# control_board_v006_Rev5.net
KiCad netlist of a schematic drawn in EAGLE
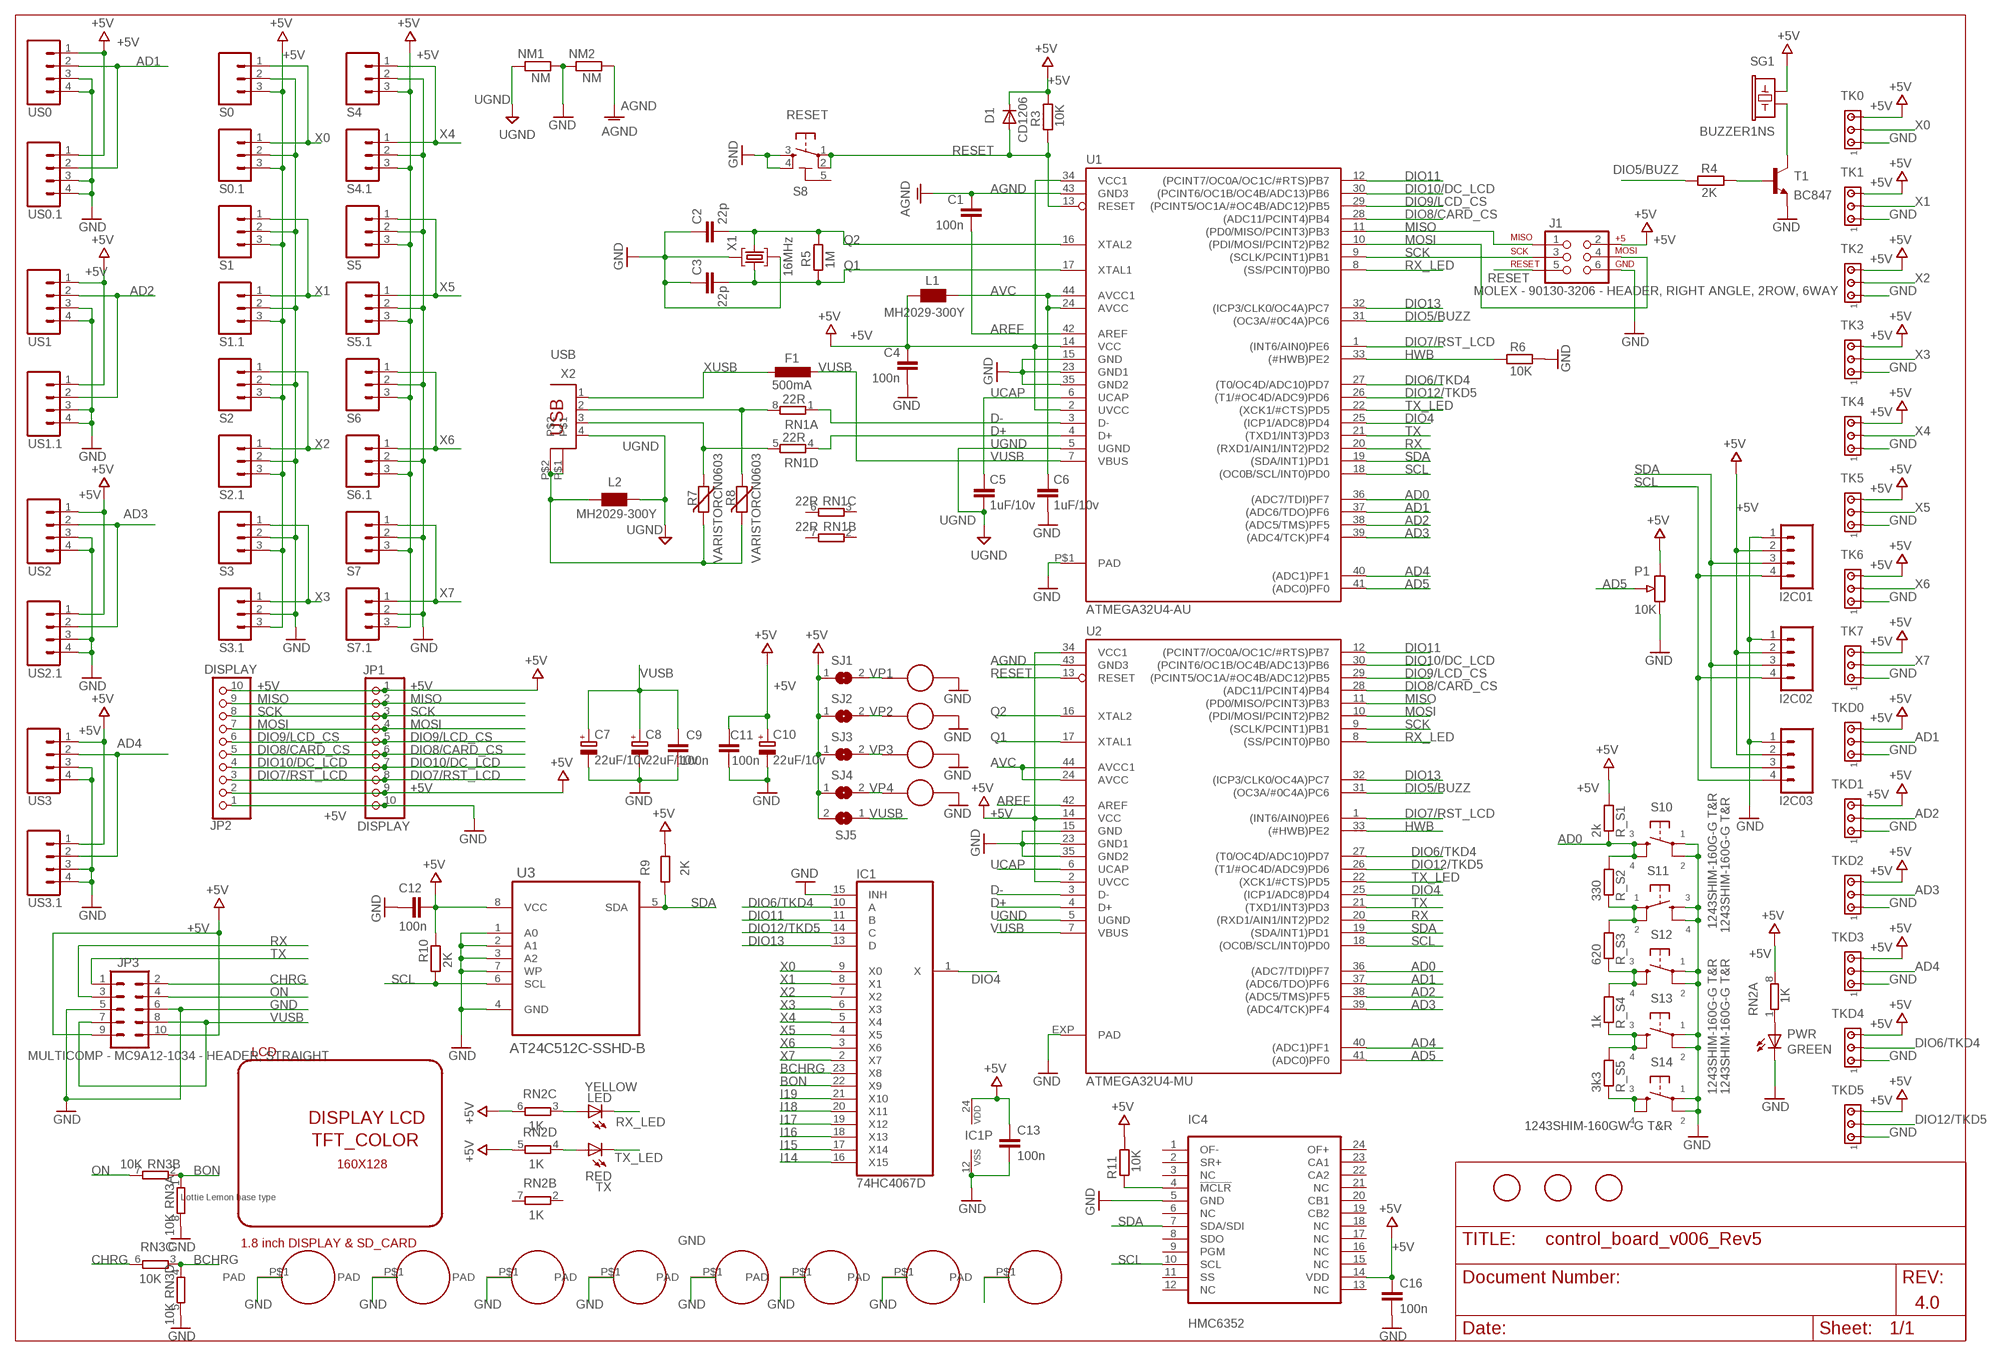
[diagram p0: schematic, sheet 1]

(export (version "E")
  (design (tool "Eeschema 10.0.6"))
  (components
    (comp (ref "1")
      (value "FIDUCIALMOUNT")
      (footprint "eagle-import:FIDUCIA-MOUNT")
      (libsource (lib "eagle-import") (part "FIDUCIALMOUNT"))
    )
    (comp (ref "2")
      (value "FIDUCIALMOUNT")
      (footprint "eagle-import:FIDUCIA-MOUNT")
      (libsource (lib "eagle-import") (part "FIDUCIALMOUNT"))
    )
    (comp (ref "3")
      (value "FIDUCIALMOUNT")
      (footprint "eagle-import:FIDUCIA-MOUNT")
      (libsource (lib "eagle-import") (part "FIDUCIALMOUNT"))
    )
    (comp (ref "C1")
      (value "100n")
      (footprint "eagle-import:C0603-ROUND")
      (libsource (lib "eagle-import") (part "C-EUC0603"))
    )
    (comp (ref "C2")
      (value "22p")
      (footprint "eagle-import:C0603-ROUND")
      (libsource (lib "eagle-import") (part "C-EUC0603"))
    )
    (comp (ref "C3")
      (value "22p")
      (footprint "eagle-import:C0603-ROUND")
      (libsource (lib "eagle-import") (part "C-EUC0603"))
    )
    (comp (ref "C4")
      (value "100n")
      (footprint "eagle-import:C0603-ROUND")
      (libsource (lib "eagle-import") (part "C-EUC0603"))
    )
    (comp (ref "C5")
      (value "1uF/10v")
      (footprint "eagle-import:C0603-ROUND")
      (libsource (lib "eagle-import") (part "C-EUC0603"))
    )
    (comp (ref "C6")
      (value "1uF/10v")
      (footprint "eagle-import:C0603-ROUND")
      (libsource (lib "eagle-import") (part "C-EUC0603"))
    )
    (comp (ref "C7")
      (value "22uF/10v")
      (footprint "eagle-import:SMC_B")
      (libsource (lib "eagle-import") (part "CPOL-EUSMCB"))
    )
    (comp (ref "C8")
      (value "22uF/10v")
      (footprint "eagle-import:SMC_B")
      (libsource (lib "eagle-import") (part "CPOL-EUSMCB"))
    )
    (comp (ref "C9")
      (value "100n")
      (footprint "eagle-import:C0603-ROUND")
      (libsource (lib "eagle-import") (part "C-EUC0603"))
    )
    (comp (ref "C10")
      (value "22uF/10v")
      (footprint "eagle-import:SMC_B")
      (libsource (lib "eagle-import") (part "CPOL-EUSMCB"))
    )
    (comp (ref "C11")
      (value "100n")
      (footprint "eagle-import:C0603-ROUND")
      (libsource (lib "eagle-import") (part "C-EUC0603"))
    )
    (comp (ref "C12")
      (value "100n")
      (footprint "eagle-import:C0603-ROUND")
      (libsource (lib "eagle-import") (part "C-EUC0603"))
    )
    (comp (ref "C13")
      (value "100n")
      (footprint "eagle-import:C0603-ROUND")
      (libsource (lib "eagle-import") (part "C-EUC0603"))
    )
    (comp (ref "C16")
      (value "100n")
      (footprint "eagle-import:C0603-ROUND")
      (libsource (lib "eagle-import") (part "C-EUC0603"))
    )
    (comp (ref "D1")
      (value "CD1206")
      (footprint "eagle-import:MINIMELF")
      (libsource (lib "eagle-import") (part "DIODE-MINIMELF"))
    )
    (comp (ref "F1")
      (value "500mA")
      (footprint "eagle-import:L1812")
      (libsource (lib "eagle-import") (part "L-EUL1812"))
    )
    (comp (ref "G1")
      (value "LOTTIE_LEMON_BASE_TYPE")
      (footprint "eagle-import:BASE_ROBOT_001")
      (libsource (lib "eagle-import") (part "LOTTIE_LEMON_BASE_TYPE"))
    )
    (comp (ref "H1")
      (value "2.5-MOUNTING-HOLE")
      (footprint "eagle-import:2.5PAD")
      (libsource (lib "eagle-import") (part "2.5-MOUNTING-HOLE"))
    )
    (comp (ref "H2")
      (value "2.5-MOUNTING-HOLE")
      (footprint "eagle-import:2.5PAD")
      (libsource (lib "eagle-import") (part "2.5-MOUNTING-HOLE"))
    )
    (comp (ref "H3")
      (value "2.5-MOUNTING-HOLE")
      (footprint "eagle-import:2.5PAD")
      (libsource (lib "eagle-import") (part "2.5-MOUNTING-HOLE"))
    )
    (comp (ref "H4")
      (value "2.5-MOUNTING-HOLE")
      (footprint "eagle-import:2.5PAD")
      (libsource (lib "eagle-import") (part "2.5-MOUNTING-HOLE"))
    )
    (comp (ref "H5")
      (value "2.5-MOUNTING-HOLE")
      (footprint "eagle-import:2.5PAD")
      (libsource (lib "eagle-import") (part "2.5-MOUNTING-HOLE"))
    )
    (comp (ref "H6")
      (value "2.5-MOUNTING-HOLE")
      (footprint "eagle-import:2.5PAD")
      (libsource (lib "eagle-import") (part "2.5-MOUNTING-HOLE"))
    )
    (comp (ref "H7")
      (value "2.5-MOUNTING-HOLE")
      (footprint "eagle-import:2.5PAD")
      (libsource (lib "eagle-import") (part "2.5-MOUNTING-HOLE"))
    )
    (comp (ref "H8")
      (value "2.5-MOUNTING-HOLE")
      (footprint "eagle-import:2.5PAD")
      (libsource (lib "eagle-import") (part "2.5-MOUNTING-HOLE"))
    )
    (comp (ref "I2C01")
      (value "M04PTH")
      (footprint "eagle-import:1X04")
      (libsource (lib "eagle-import") (part "M04PTH"))
    )
    (comp (ref "I2C02")
      (value "M04PTH")
      (footprint "eagle-import:1X04")
      (libsource (lib "eagle-import") (part "M04PTH"))
    )
    (comp (ref "I2C03")
      (value "M04PTH")
      (footprint "eagle-import:1X04")
      (libsource (lib "eagle-import") (part "M04PTH"))
    )
    (comp (ref "IC1")
      (value "74HC4067D")
      (footprint "eagle-import:SO24W")
      (libsource (lib "eagle-import") (part "4067D"))
    )
    (comp (ref "IC4")
      (value "HMC6352")
      (footprint "eagle-import:HMC6352")
      (libsource (lib "eagle-import") (part "HMC6352"))
    )
    (comp (ref "J1")
      (value "MOLEX - 90130-3206 - HEADER, RIGHT ANGLE, 2ROW, 6WAY")
      (footprint "eagle-import:2X3")
      (libsource (lib "eagle-import") (part "AVR_SPI_PRG_6PTH"))
    )
    (comp (ref "JP1")
      (value "DISPLAY")
      (footprint "eagle-import:1X10-TH")
      (libsource (lib "eagle-import") (part "PINHD-1X10TH"))
    )
    (comp (ref "JP2")
      (value "DISPLAY")
      (footprint "eagle-import:1X10-TH")
      (libsource (lib "eagle-import") (part "PINHD-1X10TH"))
    )
    (comp (ref "JP3")
      (value "MULTICOMP - MC9A12-1034 - HEADER, STRAIGHT")
      (footprint "eagle-import:2X5-SHROUDED_LOCK")
      (libsource (lib "eagle-import") (part "M05X2SHD_LOCK"))
    )
    (comp (ref "L1")
      (value "MH2029-300Y")
      (footprint "eagle-import:0805")
      (libsource (lib "eagle-import") (part "WE-CBF_0805"))
    )
    (comp (ref "L2")
      (value "MH2029-300Y")
      (footprint "eagle-import:0805")
      (libsource (lib "eagle-import") (part "WE-CBF_0805"))
    )
    (comp (ref "LCD")
      (value "1.8 inch DISPLAY & SD_CARD")
      (footprint "eagle-import:1.8-LCD")
      (libsource (lib "eagle-import") (part "1.8-COLOR_TFT-LCD_DISPLAY_&_MICRO-SD"))
    )
    (comp (ref "LED")
      (value "YELLOW")
      (footprint "eagle-import:CHIP-LED0805")
      (libsource (lib "eagle-import") (part "LEDCHIP-LED0805"))
    )
    (comp (ref "NM1")
      (value "NM")
      (footprint "eagle-import:R0805")
      (libsource (lib "eagle-import") (part "resistor_R-EU_R0805"))
    )
    (comp (ref "NM2")
      (value "NM")
      (footprint "eagle-import:R0805")
      (libsource (lib "eagle-import") (part "resistor_R-EU_R0805"))
    )
    (comp (ref "P1")
      (value "10K")
      (footprint "eagle-import:POT-V")
      (libsource (lib "eagle-import") (part "POT-VERTICAL"))
    )
    (comp (ref "PTZ1")
      (value "LOTTIE_LEMON_PADS_SUP")
      (footprint "eagle-import:PADS_LOTTIE_LEMON_SUP")
      (libsource (lib "eagle-import") (part "LOTTIE_LEMON_PADS_SUP"))
    )
    (comp (ref "PTZ2")
      (value "LOTTIE_LEMON_PADS_SUP")
      (footprint "eagle-import:PADS_LOTTIE_LEMON_SUP")
      (libsource (lib "eagle-import") (part "LOTTIE_LEMON_PADS_SUP"))
    )
    (comp (ref "PTZ3")
      (value "LOTTIE_LEMON_PADS_SUP1")
      (footprint "eagle-import:PADS_LOTTIE_LEMON_SUP")
      (libsource (lib "eagle-import") (part "LOTTIE_LEMON_PADS_SUP1"))
    )
    (comp (ref "PTZ4")
      (value "LOTTIE_LEMON_PADS_SUP1")
      (footprint "eagle-import:PADS_LOTTIE_LEMON_SUP")
      (libsource (lib "eagle-import") (part "LOTTIE_LEMON_PADS_SUP1"))
    )
    (comp (ref "PWR")
      (value "LEDCHIP-LED0805")
      (footprint "eagle-import:CHIP-LED0805")
      (libsource (lib "eagle-import") (part "LEDCHIP-LED0805"))
    )
    (comp (ref "R3")
      (value "10K")
      (footprint "eagle-import:R0603-ROUND")
      (libsource (lib "eagle-import") (part "R-EU_R0603"))
    )
    (comp (ref "R4")
      (value "2K")
      (footprint "eagle-import:R0603-ROUND")
      (libsource (lib "eagle-import") (part "R-EU_R0603"))
    )
    (comp (ref "R5")
      (value "1M")
      (footprint "eagle-import:R0603-ROUND")
      (libsource (lib "eagle-import") (part "R-EU_R0603"))
    )
    (comp (ref "R6")
      (value "10K")
      (footprint "eagle-import:R0603-ROUND")
      (libsource (lib "eagle-import") (part "R-EU_R0603"))
    )
    (comp (ref "R7")
      (value "VARISTORCN0603")
      (footprint "eagle-import:CT_CN0603")
      (libsource (lib "eagle-import") (part "VARISTORCN0603"))
    )
    (comp (ref "R8")
      (value "VARISTORCN0603")
      (footprint "eagle-import:CT_CN0603")
      (libsource (lib "eagle-import") (part "VARISTORCN0603"))
    )
    (comp (ref "R9")
      (value "2K")
      (footprint "eagle-import:R0603-ROUND")
      (libsource (lib "eagle-import") (part "R-EU_R0603"))
    )
    (comp (ref "R10")
      (value "2K")
      (footprint "eagle-import:R0603-ROUND")
      (libsource (lib "eagle-import") (part "R-EU_R0603"))
    )
    (comp (ref "R11")
      (value "10K")
      (footprint "eagle-import:R0603-ROUND")
      (libsource (lib "eagle-import") (part "R-EU_R0603"))
    )
    (comp (ref "RN1")
      (value "22R")
      (footprint "eagle-import:CAY16")
      (fields (field (name "OC_FARNELL") "unknown") (field (name "OC_NEWARK") "unknown"))
      (libsource (lib "eagle-import") (part "4R-NCAY16"))
    )
    (comp (ref "RN2")
      (value "1K")
      (footprint "eagle-import:CAY16")
      (libsource (lib "eagle-import") (part "4R-NCAY16"))
    )
    (comp (ref "RN3")
      (value "10K")
      (footprint "eagle-import:CAY16")
      (fields (field (name "OC_FARNELL") "unknown") (field (name "OC_NEWARK") "unknown"))
      (libsource (lib "eagle-import") (part "4R-NCAY16"))
    )
    (comp (ref "R_S1")
      (value "2k")
      (footprint "eagle-import:R0603-ROUND")
      (libsource (lib "eagle-import") (part "R-EU_R0603"))
    )
    (comp (ref "R_S2")
      (value "330")
      (footprint "eagle-import:R0603-ROUND")
      (libsource (lib "eagle-import") (part "R-EU_R0603"))
    )
    (comp (ref "R_S3")
      (value "620")
      (footprint "eagle-import:R0603-ROUND")
      (libsource (lib "eagle-import") (part "R-EU_R0603"))
    )
    (comp (ref "R_S4")
      (value "1k")
      (footprint "eagle-import:R0603-ROUND")
      (libsource (lib "eagle-import") (part "R-EU_R0603"))
    )
    (comp (ref "R_S5")
      (value "3k3")
      (footprint "eagle-import:R0603-ROUND")
      (libsource (lib "eagle-import") (part "R-EU_R0603"))
    )
    (comp (ref "S0")
      (value "M03PTH")
      (footprint "eagle-import:1X03")
      (libsource (lib "eagle-import") (part "M03PTH"))
    )
    (comp (ref "S0.1")
      (value "M03PTH")
      (footprint "eagle-import:1X03")
      (libsource (lib "eagle-import") (part "M03PTH"))
    )
    (comp (ref "S1")
      (value "M03PTH")
      (footprint "eagle-import:1X03")
      (libsource (lib "eagle-import") (part "M03PTH"))
    )
    (comp (ref "S1.1")
      (value "M03PTH")
      (footprint "eagle-import:1X03")
      (libsource (lib "eagle-import") (part "M03PTH"))
    )
    (comp (ref "S2")
      (value "M03PTH")
      (footprint "eagle-import:1X03")
      (libsource (lib "eagle-import") (part "M03PTH"))
    )
    (comp (ref "S2.1")
      (value "M03PTH")
      (footprint "eagle-import:1X03")
      (libsource (lib "eagle-import") (part "M03PTH"))
    )
    (comp (ref "S3")
      (value "M03PTH")
      (footprint "eagle-import:1X03")
      (libsource (lib "eagle-import") (part "M03PTH"))
    )
    (comp (ref "S3.1")
      (value "M03PTH")
      (footprint "eagle-import:1X03")
      (libsource (lib "eagle-import") (part "M03PTH"))
    )
    (comp (ref "S4")
      (value "M03PTH")
      (footprint "eagle-import:1X03")
      (libsource (lib "eagle-import") (part "M03PTH"))
    )
    (comp (ref "S4.1")
      (value "M03PTH")
      (footprint "eagle-import:1X03")
      (libsource (lib "eagle-import") (part "M03PTH"))
    )
    (comp (ref "S5")
      (value "M03PTH")
      (footprint "eagle-import:1X03")
      (libsource (lib "eagle-import") (part "M03PTH"))
    )
    (comp (ref "S5.1")
      (value "M03PTH")
      (footprint "eagle-import:1X03")
      (libsource (lib "eagle-import") (part "M03PTH"))
    )
    (comp (ref "S6")
      (value "M03PTH")
      (footprint "eagle-import:1X03")
      (libsource (lib "eagle-import") (part "M03PTH"))
    )
    (comp (ref "S6.1")
      (value "M03PTH")
      (footprint "eagle-import:1X03")
      (libsource (lib "eagle-import") (part "M03PTH"))
    )
    (comp (ref "S7")
      (value "M03PTH")
      (footprint "eagle-import:1X03")
      (libsource (lib "eagle-import") (part "M03PTH"))
    )
    (comp (ref "S7.1")
      (value "M03PTH")
      (footprint "eagle-import:1X03")
      (libsource (lib "eagle-import") (part "M03PTH"))
    )
    (comp (ref "S8")
      (value "RESET")
      (footprint "eagle-import:TS42")
      (libsource (lib "eagle-import") (part "TS42"))
    )
    (comp (ref "S10")
      (value "1243SHIM-160G-G T&R")
      (footprint "eagle-import:TACTILE-SMD-12MM")
      (libsource (lib "eagle-import") (part "TACTILE_SWITCHTACTILE_SWITCH_SMD-12MM"))
    )
    (comp (ref "S11")
      (value "1243SHIM-160G-G T&R")
      (footprint "eagle-import:TACTILE-SMD-12MM")
      (libsource (lib "eagle-import") (part "TACTILE_SWITCHTACTILE_SWITCH_SMD-12MM"))
    )
    (comp (ref "S12")
      (value "1243SHIM-160G-G T&R")
      (footprint "eagle-import:TACTILE-SMD-12MM")
      (libsource (lib "eagle-import") (part "TACTILE_SWITCHTACTILE_SWITCH_SMD-12MM"))
    )
    (comp (ref "S13")
      (value "1243SHIM-160G-G T&R")
      (footprint "eagle-import:TACTILE-SMD-12MM")
      (libsource (lib "eagle-import") (part "TACTILE_SWITCHTACTILE_SWITCH_SMD-12MM"))
    )
    (comp (ref "S14")
      (value "1243SHIM-160GW-G T&R")
      (footprint "eagle-import:TACTILE-SMD-12MM")
      (libsource (lib "eagle-import") (part "TACTILE_SWITCHTACTILE_SWITCH_SMD-12MM"))
    )
    (comp (ref "SG1")
      (value "BUZZER1NS")
      (footprint "eagle-import:BUZZER-12MM-NS")
      (libsource (lib "eagle-import") (part "BUZZER1NS"))
    )
    (comp (ref "SJ1") (value "SJ") (footprint "eagle-import:SJ") (libsource (lib "eagle-import") (part "SJ")))
    (comp (ref "SJ2") (value "SJ") (footprint "eagle-import:SJ") (libsource (lib "eagle-import") (part "SJ")))
    (comp (ref "SJ3") (value "SJ") (footprint "eagle-import:SJ") (libsource (lib "eagle-import") (part "SJ")))
    (comp (ref "SJ4") (value "SJ") (footprint "eagle-import:SJ") (libsource (lib "eagle-import") (part "SJ")))
    (comp (ref "SJ5")
      (value "SJL")
      (footprint "eagle-import:SJL")
      (libsource (lib "eagle-import") (part "SJL"))
    )
    (comp (ref "T1")
      (value "BC847")
      (footprint "eagle-import:SOT23")
      (libsource (lib "eagle-import") (part "BC847"))
    )
    (comp (ref "TK0")
      (value "MTA03-100")
      (footprint "eagle-import:10X03MTA")
      (libsource (lib "eagle-import") (part "MTA03-100"))
    )
    (comp (ref "TK1")
      (value "MTA03-100")
      (footprint "eagle-import:10X03MTA")
      (libsource (lib "eagle-import") (part "MTA03-100"))
    )
    (comp (ref "TK2")
      (value "MTA03-100")
      (footprint "eagle-import:10X03MTA")
      (libsource (lib "eagle-import") (part "MTA03-100"))
    )
    (comp (ref "TK3")
      (value "MTA03-100")
      (footprint "eagle-import:10X03MTA")
      (libsource (lib "eagle-import") (part "MTA03-100"))
    )
    (comp (ref "TK4")
      (value "MTA03-100")
      (footprint "eagle-import:10X03MTA")
      (libsource (lib "eagle-import") (part "MTA03-100"))
    )
    (comp (ref "TK5")
      (value "MTA03-100")
      (footprint "eagle-import:10X03MTA")
      (libsource (lib "eagle-import") (part "MTA03-100"))
    )
    (comp (ref "TK6")
      (value "MTA03-100")
      (footprint "eagle-import:10X03MTA")
      (libsource (lib "eagle-import") (part "MTA03-100"))
    )
    (comp (ref "TK7")
      (value "MTA03-100")
      (footprint "eagle-import:10X03MTA")
      (libsource (lib "eagle-import") (part "MTA03-100"))
    )
    (comp (ref "TKD0")
      (value "MTA03-100")
      (footprint "eagle-import:10X03MTA")
      (libsource (lib "eagle-import") (part "MTA03-100"))
    )
    (comp (ref "TKD1")
      (value "MTA03-100")
      (footprint "eagle-import:10X03MTA")
      (libsource (lib "eagle-import") (part "MTA03-100"))
    )
    (comp (ref "TKD2")
      (value "MTA03-100")
      (footprint "eagle-import:10X03MTA")
      (libsource (lib "eagle-import") (part "MTA03-100"))
    )
    (comp (ref "TKD3")
      (value "MTA03-100")
      (footprint "eagle-import:10X03MTA")
      (libsource (lib "eagle-import") (part "MTA03-100"))
    )
    (comp (ref "TKD4")
      (value "MTA03-100")
      (footprint "eagle-import:10X03MTA")
      (libsource (lib "eagle-import") (part "MTA03-100"))
    )
    (comp (ref "TKD5")
      (value "MTA03-100")
      (footprint "eagle-import:10X03MTA")
      (libsource (lib "eagle-import") (part "MTA03-100"))
    )
    (comp (ref "TX")
      (value "RED")
      (footprint "eagle-import:CHIP-LED0805")
      (libsource (lib "eagle-import") (part "LEDCHIP-LED0805"))
    )
    (comp (ref "U1")
      (value "ATMEGA32U4-AU")
      (footprint "eagle-import:TQFP44-PAD")
      (libsource (lib "eagle-import") (part "ATMEGA32U4-XUAU"))
    )
    (comp (ref "U2")
      (value "ATMEGA32U4-MU")
      (footprint "eagle-import:QFN44ML7X7")
      (libsource (lib "eagle-import") (part "ATMEGA32U4-XUMU"))
    )
    (comp (ref "U3")
      (value "AT24C512C-SSHD-B")
      (footprint "eagle-import:SOIC127P600X175-8N")
      (fields (field (name "MPN") "AT24C128BN-SH-B"))
      (libsource (lib "eagle-import") (part "AT24C128BN-SH-B"))
    )
    (comp (ref "US0")
      (value "M04PTH")
      (footprint "eagle-import:1X04")
      (libsource (lib "eagle-import") (part "M04PTH"))
    )
    (comp (ref "US0.1")
      (value "M04PTH")
      (footprint "eagle-import:1X04")
      (libsource (lib "eagle-import") (part "M04PTH"))
    )
    (comp (ref "US1")
      (value "M04PTH")
      (footprint "eagle-import:1X04")
      (libsource (lib "eagle-import") (part "M04PTH"))
    )
    (comp (ref "US1.1")
      (value "M04PTH")
      (footprint "eagle-import:1X04")
      (libsource (lib "eagle-import") (part "M04PTH"))
    )
    (comp (ref "US2")
      (value "M04PTH")
      (footprint "eagle-import:1X04")
      (libsource (lib "eagle-import") (part "M04PTH"))
    )
    (comp (ref "US2.1")
      (value "M04PTH")
      (footprint "eagle-import:1X04")
      (libsource (lib "eagle-import") (part "M04PTH"))
    )
    (comp (ref "US3")
      (value "M04PTH")
      (footprint "eagle-import:1X04")
      (libsource (lib "eagle-import") (part "M04PTH"))
    )
    (comp (ref "US3.1")
      (value "M04PTH")
      (footprint "eagle-import:1X04")
      (libsource (lib "eagle-import") (part "M04PTH"))
    )
    (comp (ref "X1")
      (value "16MHz")
      (footprint "eagle-import:CRYSTAL-3.2-2.5")
      (libsource (lib "eagle-import") (part "CRYSTAL-3.2-2.5"))
    )
    (comp (ref "X2")
      (value "USB")
      (footprint "eagle-import:PN61729")
      (libsource (lib "eagle-import") (part "PN61729"))
    )
  )
  (nets
    (net (code "1") (name "+5V") (class "Default")
      (node (ref "C10") (pin "+") (pinfunction "+_+") (pintype "passive"))
      (node (ref "C11") (pin "1") (pinfunction "1_1") (pintype "passive"))
      (node (ref "C12") (pin "1") (pinfunction "1_1") (pintype "passive"))
      (node (ref "C13") (pin "1") (pinfunction "1_1") (pintype "passive"))
      (node (ref "C16") (pin "1") (pinfunction "1_1") (pintype "passive"))
      (node (ref "C4") (pin "1") (pinfunction "1_1") (pintype "passive"))
      (node (ref "D1") (pin "C") (pinfunction "C_C") (pintype "passive"))
      (node (ref "I2C01") (pin "2") (pinfunction "2_2") (pintype "passive"))
      (node (ref "I2C02") (pin "2") (pinfunction "2_2") (pintype "passive"))
      (node (ref "I2C03") (pin "2") (pinfunction "2_2") (pintype "passive"))
      (node (ref "IC1") (pin "24") (pinfunction "VDD_24") (pintype "power_in"))
      (node (ref "IC4") (pin "14") (pinfunction "VDD_14") (pintype "power_in"))
      (node (ref "J1") (pin "2") (pinfunction "2_2") (pintype "passive"))
      (node (ref "JP1") (pin "1") (pinfunction "1_1") (pintype "passive"))
      (node (ref "JP1") (pin "9") (pinfunction "9_9") (pintype "passive"))
      (node (ref "JP2") (pin "10") (pinfunction "10_10") (pintype "passive"))
      (node (ref "JP2") (pin "2") (pinfunction "2_2") (pintype "passive"))
      (node (ref "JP3") (pin "10") (pinfunction "10_10") (pintype "passive"))
      (node (ref "JP3") (pin "9") (pinfunction "9_9") (pintype "passive"))
      (node (ref "L1") (pin "2") (pinfunction "2_2") (pintype "passive"))
      (node (ref "P1") (pin "B") (pinfunction "B_B") (pintype "passive"))
      (node (ref "R10") (pin "1") (pinfunction "1_1") (pintype "passive"))
      (node (ref "R11") (pin "1") (pinfunction "1_1") (pintype "passive"))
      (node (ref "R3") (pin "1") (pinfunction "1_1") (pintype "passive"))
      (node (ref "R9") (pin "2") (pinfunction "2_2") (pintype "passive"))
      (node (ref "RN2") (pin "5") (pinfunction "2_5") (pintype "passive"))
      (node (ref "RN2") (pin "6") (pinfunction "2_6") (pintype "passive"))
      (node (ref "RN2") (pin "8") (pinfunction "2_8") (pintype "passive"))
      (node (ref "R_S1") (pin "2") (pinfunction "2_2") (pintype "passive"))
      (node (ref "S0") (pin "3") (pinfunction "3_3") (pintype "passive"))
      (node (ref "S0.1") (pin "3") (pinfunction "3_3") (pintype "passive"))
      (node (ref "S1") (pin "3") (pinfunction "3_3") (pintype "passive"))
      (node (ref "S1.1") (pin "3") (pinfunction "3_3") (pintype "passive"))
      (node (ref "S2") (pin "3") (pinfunction "3_3") (pintype "passive"))
      (node (ref "S2.1") (pin "3") (pinfunction "3_3") (pintype "passive"))
      (node (ref "S3") (pin "3") (pinfunction "3_3") (pintype "passive"))
      (node (ref "S3.1") (pin "3") (pinfunction "3_3") (pintype "passive"))
      (node (ref "S4") (pin "3") (pinfunction "3_3") (pintype "passive"))
      (node (ref "S4.1") (pin "3") (pinfunction "3_3") (pintype "passive"))
      (node (ref "S5") (pin "3") (pinfunction "3_3") (pintype "passive"))
      (node (ref "S5.1") (pin "3") (pinfunction "3_3") (pintype "passive"))
      (node (ref "S6") (pin "3") (pinfunction "3_3") (pintype "passive"))
      (node (ref "S6.1") (pin "3") (pinfunction "3_3") (pintype "passive"))
      (node (ref "S7") (pin "3") (pinfunction "3_3") (pintype "passive"))
      (node (ref "S7.1") (pin "3") (pinfunction "3_3") (pintype "passive"))
      (node (ref "SG1") (pin "+") (pinfunction "1_+") (pintype "passive"))
      (node (ref "SJ1") (pin "1") (pinfunction "1_1") (pintype "passive"))
      (node (ref "SJ2") (pin "1") (pinfunction "1_1") (pintype "passive"))
      (node (ref "SJ3") (pin "1") (pinfunction "1_1") (pintype "passive"))
      (node (ref "SJ4") (pin "1") (pinfunction "1_1") (pintype "passive"))
      (node (ref "SJ5") (pin "2") (pinfunction "2_2") (pintype "passive"))
      (node (ref "TK0") (pin "3") (pinfunction "3_3") (pintype "passive"))
      (node (ref "TK1") (pin "3") (pinfunction "3_3") (pintype "passive"))
      (node (ref "TK2") (pin "3") (pinfunction "3_3") (pintype "passive"))
      (node (ref "TK3") (pin "3") (pinfunction "3_3") (pintype "passive"))
      (node (ref "TK4") (pin "3") (pinfunction "3_3") (pintype "passive"))
      (node (ref "TK5") (pin "3") (pinfunction "3_3") (pintype "passive"))
      (node (ref "TK6") (pin "3") (pinfunction "3_3") (pintype "passive"))
      (node (ref "TK7") (pin "3") (pinfunction "3_3") (pintype "passive"))
      (node (ref "TKD0") (pin "3") (pinfunction "3_3") (pintype "passive"))
      (node (ref "TKD1") (pin "3") (pinfunction "3_3") (pintype "passive"))
      (node (ref "TKD2") (pin "3") (pinfunction "3_3") (pintype "passive"))
      (node (ref "TKD3") (pin "3") (pinfunction "3_3") (pintype "passive"))
      (node (ref "TKD4") (pin "3") (pinfunction "3_3") (pintype "passive"))
      (node (ref "TKD5") (pin "3") (pinfunction "3_3") (pintype "passive"))
      (node (ref "U1") (pin "14") (pinfunction "VCC_14") (pintype "power_in"))
      (node (ref "U1") (pin "2") (pinfunction "UVCC_2") (pintype "power_in"))
      (node (ref "U1") (pin "34") (pinfunction "VCC1_34") (pintype "power_in"))
      (node (ref "U2") (pin "14") (pinfunction "VCC_14") (pintype "power_in"))
      (node (ref "U2") (pin "2") (pinfunction "UVCC_2") (pintype "power_in"))
      (node (ref "U2") (pin "34") (pinfunction "VCC1_34") (pintype "power_in"))
      (node (ref "U3") (pin "8") (pinfunction "VCC_8") (pintype "power_in"))
      (node (ref "US0") (pin "1") (pinfunction "1_1") (pintype "passive"))
      (node (ref "US0.1") (pin "1") (pinfunction "1_1") (pintype "passive"))
      (node (ref "US1") (pin "1") (pinfunction "1_1") (pintype "passive"))
      (node (ref "US1.1") (pin "1") (pinfunction "1_1") (pintype "passive"))
      (node (ref "US2") (pin "1") (pinfunction "1_1") (pintype "passive"))
      (node (ref "US2.1") (pin "1") (pinfunction "1_1") (pintype "passive"))
      (node (ref "US3") (pin "1") (pinfunction "1_1") (pintype "passive"))
      (node (ref "US3.1") (pin "1") (pinfunction "1_1") (pintype "passive"))
    )
    (net (code "2") (name "/5-GND") (class "Default")
      (node (ref "S8") (pin "5") (pinfunction "5-GND_5") (pintype "power_in"))
    )
    (net (code "3") (name "/AD0") (class "Default")
      (node (ref "R_S1") (pin "1") (pinfunction "1_1") (pintype "passive"))
      (node (ref "R_S2") (pin "2") (pinfunction "2_2") (pintype "passive"))
      (node (ref "S10") (pin "P$3") (pinfunction "3_P$3") (pintype "passive"))
      (node (ref "S10") (pin "P$4") (pinfunction "4_P$4") (pintype "passive"))
      (node (ref "U1") (pin "36") (pinfunction "(ADC7/TDI)PF7_36") (pintype "bidirectional"))
      (node (ref "U2") (pin "36") (pinfunction "(ADC7/TDI)PF7_36") (pintype "bidirectional"))
    )
    (net (code "4") (name "/AD1") (class "Default")
      (node (ref "TKD0") (pin "2") (pinfunction "2_2") (pintype "passive"))
      (node (ref "U1") (pin "37") (pinfunction "(ADC6/TDO)PF6_37") (pintype "bidirectional"))
      (node (ref "U2") (pin "37") (pinfunction "(ADC6/TDO)PF6_37") (pintype "bidirectional"))
      (node (ref "US0") (pin "2") (pinfunction "2_2") (pintype "passive"))
      (node (ref "US0.1") (pin "2") (pinfunction "2_2") (pintype "passive"))
    )
    (net (code "5") (name "/AD2") (class "Default")
      (node (ref "TKD1") (pin "2") (pinfunction "2_2") (pintype "passive"))
      (node (ref "U1") (pin "38") (pinfunction "(ADC5/TMS)PF5_38") (pintype "bidirectional"))
      (node (ref "U2") (pin "38") (pinfunction "(ADC5/TMS)PF5_38") (pintype "bidirectional"))
      (node (ref "US1") (pin "2") (pinfunction "2_2") (pintype "passive"))
      (node (ref "US1.1") (pin "2") (pinfunction "2_2") (pintype "passive"))
    )
    (net (code "6") (name "/AD3") (class "Default")
      (node (ref "TKD2") (pin "2") (pinfunction "2_2") (pintype "passive"))
      (node (ref "U1") (pin "39") (pinfunction "(ADC4/TCK)PF4_39") (pintype "bidirectional"))
      (node (ref "U2") (pin "39") (pinfunction "(ADC4/TCK)PF4_39") (pintype "bidirectional"))
      (node (ref "US2") (pin "2") (pinfunction "2_2") (pintype "passive"))
      (node (ref "US2.1") (pin "2") (pinfunction "2_2") (pintype "passive"))
    )
    (net (code "7") (name "/AD4") (class "Default")
      (node (ref "TKD3") (pin "2") (pinfunction "2_2") (pintype "passive"))
      (node (ref "U1") (pin "40") (pinfunction "(ADC1)PF1_40") (pintype "bidirectional"))
      (node (ref "U2") (pin "40") (pinfunction "(ADC1)PF1_40") (pintype "bidirectional"))
      (node (ref "US3") (pin "2") (pinfunction "2_2") (pintype "passive"))
      (node (ref "US3.1") (pin "2") (pinfunction "2_2") (pintype "passive"))
    )
    (net (code "8") (name "/AD5") (class "Default")
      (node (ref "P1") (pin "C") (pinfunction "C_C") (pintype "passive"))
      (node (ref "U1") (pin "41") (pinfunction "(ADC0)PF0_41") (pintype "bidirectional"))
      (node (ref "U2") (pin "41") (pinfunction "(ADC0)PF0_41") (pintype "bidirectional"))
    )
    (net (code "9") (name "/AREF") (class "Default")
      (node (ref "C1") (pin "2") (pinfunction "2_2") (pintype "passive"))
      (node (ref "U1") (pin "42") (pinfunction "AREF_42") (pintype "power_in"))
      (node (ref "U2") (pin "42") (pinfunction "AREF_42") (pintype "power_in"))
    )
    (net (code "10") (name "/AVC") (class "Default")
      (node (ref "C6") (pin "1") (pinfunction "1_1") (pintype "passive"))
      (node (ref "L1") (pin "1") (pinfunction "1_1") (pintype "passive"))
      (node (ref "U1") (pin "24") (pinfunction "AVCC_24") (pintype "power_in"))
      (node (ref "U1") (pin "44") (pinfunction "AVCC1_44") (pintype "power_in"))
      (node (ref "U2") (pin "24") (pinfunction "AVCC_24") (pintype "power_in"))
      (node (ref "U2") (pin "44") (pinfunction "AVCC1_44") (pintype "power_in"))
    )
    (net (code "11") (name "/BCHRG") (class "Default")
      (node (ref "IC1") (pin "23") (pinfunction "X8_23") (pintype "input"))
      (node (ref "RN3") (pin "3") (pinfunction "1_3") (pintype "passive"))
      (node (ref "RN3") (pin "4") (pinfunction "1_4") (pintype "passive"))
    )
    (net (code "12") (name "/BON") (class "Default")
      (node (ref "IC1") (pin "22") (pinfunction "X9_22") (pintype "input"))
      (node (ref "RN3") (pin "1") (pinfunction "1_1") (pintype "passive"))
      (node (ref "RN3") (pin "2") (pinfunction "1_2") (pintype "passive"))
    )
    (net (code "13") (name "/CHRG") (class "Default")
      (node (ref "JP3") (pin "2") (pinfunction "2_2") (pintype "passive"))
      (node (ref "RN3") (pin "6") (pinfunction "2_6") (pintype "passive"))
    )
    (net (code "14") (name "/D+") (class "Default")
      (node (ref "RN1") (pin "4") (pinfunction "1_4") (pintype "passive"))
      (node (ref "U1") (pin "4") (pinfunction "D+_4") (pintype "bidirectional"))
      (node (ref "U2") (pin "4") (pinfunction "D+_4") (pintype "bidirectional"))
    )
    (net (code "15") (name "/D-") (class "Default")
      (node (ref "RN1") (pin "1") (pinfunction "1_1") (pintype "passive"))
      (node (ref "U1") (pin "3") (pinfunction "D-_3") (pintype "bidirectional"))
      (node (ref "U2") (pin "3") (pinfunction "D-_3") (pintype "bidirectional"))
    )
    (net (code "16") (name "/DIO4") (class "Default")
      (node (ref "IC1") (pin "1") (pinfunction "X_1") (pintype "output"))
      (node (ref "U1") (pin "25") (pinfunction "(ICP1/ADC8)PD4_25") (pintype "bidirectional"))
      (node (ref "U2") (pin "25") (pinfunction "(ICP1/ADC8)PD4_25") (pintype "bidirectional"))
    )
    (net (code "17") (name "/DIO5{slash}BUZZ") (class "Default")
      (node (ref "R4") (pin "2") (pinfunction "2_2") (pintype "passive"))
      (node (ref "U1") (pin "31") (pinfunction "(OC3A/#0C4A)PC6_31") (pintype "bidirectional"))
      (node (ref "U2") (pin "31") (pinfunction "(OC3A/#0C4A)PC6_31") (pintype "bidirectional"))
    )
    (net (code "18") (name "/DIO6{slash}TKD4") (class "Default")
      (node (ref "IC1") (pin "10") (pinfunction "A_10") (pintype "input"))
      (node (ref "TKD4") (pin "2") (pinfunction "2_2") (pintype "passive"))
      (node (ref "U1") (pin "27") (pinfunction "(T0/OC4D/ADC10)PD7_27") (pintype "bidirectional"))
      (node (ref "U2") (pin "27") (pinfunction "(T0/OC4D/ADC10)PD7_27") (pintype "bidirectional"))
    )
    (net (code "19") (name "/DIO7{slash}RST_LCD") (class "Default")
      (node (ref "JP1") (pin "8") (pinfunction "8_8") (pintype "passive"))
      (node (ref "JP2") (pin "3") (pinfunction "3_3") (pintype "passive"))
      (node (ref "U1") (pin "1") (pinfunction "(INT6/AIN0)PE6_1") (pintype "bidirectional"))
      (node (ref "U2") (pin "1") (pinfunction "(INT6/AIN0)PE6_1") (pintype "bidirectional"))
    )
    (net (code "20") (name "/DIO8{slash}CARD_CS") (class "Default")
      (node (ref "JP1") (pin "6") (pinfunction "6_6") (pintype "passive"))
      (node (ref "JP2") (pin "5") (pinfunction "5_5") (pintype "passive"))
      (node (ref "U1") (pin "28") (pinfunction "(ADC11/PCINT4)PB4_28") (pintype "bidirectional"))
      (node (ref "U2") (pin "28") (pinfunction "(ADC11/PCINT4)PB4_28") (pintype "bidirectional"))
    )
    (net (code "21") (name "/DIO9{slash}LCD_CS") (class "Default")
      (node (ref "JP1") (pin "5") (pinfunction "5_5") (pintype "passive"))
      (node (ref "JP2") (pin "6") (pinfunction "6_6") (pintype "passive"))
      (node (ref "U1") (pin "29") (pinfunction "(PCINT5/OC1A/#OC4B/ADC12)PB5_29") (pintype "bidirectional"))
      (node (ref "U2") (pin "29") (pinfunction "(PCINT5/OC1A/#OC4B/ADC12)PB5_29") (pintype "bidirectional"))
    )
    (net (code "22") (name "/DIO10{slash}DC_LCD") (class "Default")
      (node (ref "JP1") (pin "7") (pinfunction "7_7") (pintype "passive"))
      (node (ref "JP2") (pin "4") (pinfunction "4_4") (pintype "passive"))
      (node (ref "U1") (pin "30") (pinfunction "(PCINT6/OC1B/OC4B/ADC13)PB6_30") (pintype "bidirectional"))
      (node (ref "U2") (pin "30") (pinfunction "(PCINT6/OC1B/OC4B/ADC13)PB6_30") (pintype "bidirectional"))
    )
    (net (code "23") (name "/DIO11") (class "Default")
      (node (ref "IC1") (pin "11") (pinfunction "B_11") (pintype "input"))
      (node (ref "U1") (pin "12") (pinfunction "(PCINT7/OC0A/OC1C/#RTS)PB7_12") (pintype "bidirectional"))
      (node (ref "U2") (pin "12") (pinfunction "(PCINT7/OC0A/OC1C/#RTS)PB7_12") (pintype "bidirectional"))
    )
    (net (code "24") (name "/DIO12{slash}TKD5") (class "Default")
      (node (ref "IC1") (pin "14") (pinfunction "C_14") (pintype "input"))
      (node (ref "TKD5") (pin "2") (pinfunction "2_2") (pintype "passive"))
      (node (ref "U1") (pin "26") (pinfunction "(T1/#OC4D/ADC9)PD6_26") (pintype "bidirectional"))
      (node (ref "U2") (pin "26") (pinfunction "(T1/#OC4D/ADC9)PD6_26") (pintype "bidirectional"))
    )
    (net (code "25") (name "/DIO13") (class "Default")
      (node (ref "IC1") (pin "13") (pinfunction "D_13") (pintype "input"))
      (node (ref "U1") (pin "32") (pinfunction "(ICP3/CLK0/OC4A)PC7_32") (pintype "bidirectional"))
      (node (ref "U2") (pin "32") (pinfunction "(ICP3/CLK0/OC4A)PC7_32") (pintype "bidirectional"))
    )
    (net (code "26") (name "/HWB") (class "Default")
      (node (ref "R6") (pin "2") (pinfunction "2_2") (pintype "passive"))
      (node (ref "U1") (pin "33") (pinfunction "(#HWB)PE2_33") (pintype "bidirectional"))
      (node (ref "U2") (pin "33") (pinfunction "(#HWB)PE2_33") (pintype "bidirectional"))
    )
    (net (code "27") (name "/I14") (class "Default")
      (node (ref "IC1") (pin "16") (pinfunction "X15_16") (pintype "input"))
    )
    (net (code "28") (name "/I15") (class "Default")
      (node (ref "IC1") (pin "17") (pinfunction "X14_17") (pintype "input"))
    )
    (net (code "29") (name "/I16") (class "Default")
      (node (ref "IC1") (pin "18") (pinfunction "X13_18") (pintype "input"))
    )
    (net (code "30") (name "/I17") (class "Default")
      (node (ref "IC1") (pin "19") (pinfunction "X12_19") (pintype "input"))
    )
    (net (code "31") (name "/I18") (class "Default")
      (node (ref "IC1") (pin "20") (pinfunction "X11_20") (pintype "input"))
    )
    (net (code "32") (name "/I19") (class "Default")
      (node (ref "IC1") (pin "21") (pinfunction "X10_21") (pintype "input"))
    )
    (net (code "33") (name "/MISO") (class "Default")
      (node (ref "J1") (pin "1") (pinfunction "1_1") (pintype "passive"))
      (node (ref "JP1") (pin "2") (pinfunction "2_2") (pintype "passive"))
      (node (ref "JP2") (pin "9") (pinfunction "9_9") (pintype "passive"))
      (node (ref "U1") (pin "11") (pinfunction "(PD0/MISO/PCINT3)PB3_11") (pintype "bidirectional"))
      (node (ref "U2") (pin "11") (pinfunction "(PD0/MISO/PCINT3)PB3_11") (pintype "bidirectional"))
    )
    (net (code "34") (name "/MOSI") (class "Default")
      (node (ref "J1") (pin "4") (pinfunction "4_4") (pintype "passive"))
      (node (ref "JP1") (pin "4") (pinfunction "4_4") (pintype "passive"))
      (node (ref "JP2") (pin "7") (pinfunction "7_7") (pintype "passive"))
      (node (ref "U1") (pin "10") (pinfunction "(PDI/MOSI/PCINT2)PB2_10") (pintype "bidirectional"))
      (node (ref "U2") (pin "10") (pinfunction "(PDI/MOSI/PCINT2)PB2_10") (pintype "bidirectional"))
    )
    (net (code "35") (name "/ON") (class "Default")
      (node (ref "JP3") (pin "4") (pinfunction "4_4") (pintype "passive"))
      (node (ref "RN3") (pin "7") (pinfunction "2_7") (pintype "passive"))
    )
    (net (code "36") (name "/Q1") (class "Default")
      (node (ref "C3") (pin "2") (pinfunction "2_2") (pintype "passive"))
      (node (ref "R5") (pin "2") (pinfunction "2_2") (pintype "passive"))
      (node (ref "U1") (pin "17") (pinfunction "XTAL1_17") (pintype "bidirectional"))
      (node (ref "U2") (pin "17") (pinfunction "XTAL1_17") (pintype "bidirectional"))
      (node (ref "X1") (pin "1") (pinfunction "C1_1") (pintype "passive"))
    )
    (net (code "37") (name "/Q2") (class "Default")
      (node (ref "C2") (pin "2") (pinfunction "2_2") (pintype "passive"))
      (node (ref "R5") (pin "1") (pinfunction "1_1") (pintype "passive"))
      (node (ref "U1") (pin "16") (pinfunction "XTAL2_16") (pintype "bidirectional"))
      (node (ref "U2") (pin "16") (pinfunction "XTAL2_16") (pintype "bidirectional"))
      (node (ref "X1") (pin "3") (pinfunction "C2_3") (pintype "passive"))
    )
    (net (code "38") (name "/RESET") (class "Default")
      (node (ref "D1") (pin "A") (pinfunction "A_A") (pintype "passive"))
      (node (ref "J1") (pin "5") (pinfunction "5_5") (pintype "passive"))
      (node (ref "R3") (pin "2") (pinfunction "2_2") (pintype "passive"))
      (node (ref "S8") (pin "1") (pinfunction "1_1") (pintype "passive"))
      (node (ref "S8") (pin "2") (pinfunction "2_2") (pintype "passive"))
      (node (ref "U1") (pin "13") (pinfunction "RESET_13") (pintype "input"))
      (node (ref "U2") (pin "13") (pinfunction "RESET_13") (pintype "input"))
    )
    (net (code "39") (name "/RX") (class "Default")
      (node (ref "JP3") (pin "3") (pinfunction "3_3") (pintype "passive"))
      (node (ref "U1") (pin "20") (pinfunction "(RXD1/AIN1/INT2)PD2_20") (pintype "bidirectional"))
      (node (ref "U2") (pin "20") (pinfunction "(RXD1/AIN1/INT2)PD2_20") (pintype "bidirectional"))
    )
    (net (code "40") (name "/RX_LED") (class "Default")
      (node (ref "LED") (pin "C") (pinfunction "C_C") (pintype "passive"))
      (node (ref "U1") (pin "8") (pinfunction "(SS/PCINT0)PB0_8") (pintype "bidirectional"))
      (node (ref "U2") (pin "8") (pinfunction "(SS/PCINT0)PB0_8") (pintype "bidirectional"))
    )
    (net (code "41") (name "/SCK") (class "Default")
      (node (ref "J1") (pin "3") (pinfunction "3_3") (pintype "passive"))
      (node (ref "JP1") (pin "3") (pinfunction "3_3") (pintype "passive"))
      (node (ref "JP2") (pin "8") (pinfunction "8_8") (pintype "passive"))
      (node (ref "U1") (pin "9") (pinfunction "(SCLK/PCINT1)PB1_9") (pintype "bidirectional"))
      (node (ref "U2") (pin "9") (pinfunction "(SCLK/PCINT1)PB1_9") (pintype "bidirectional"))
    )
    (net (code "42") (name "/SCL") (class "Default")
      (node (ref "I2C01") (pin "4") (pinfunction "4_4") (pintype "passive"))
      (node (ref "I2C02") (pin "4") (pinfunction "4_4") (pintype "passive"))
      (node (ref "I2C03") (pin "4") (pinfunction "4_4") (pintype "passive"))
      (node (ref "IC4") (pin "10") (pinfunction "SCL_10") (pintype "input"))
      (node (ref "R10") (pin "2") (pinfunction "2_2") (pintype "passive"))
      (node (ref "U1") (pin "18") (pinfunction "(OC0B/SCL/INT0)PD0_18") (pintype "bidirectional"))
      (node (ref "U2") (pin "18") (pinfunction "(OC0B/SCL/INT0)PD0_18") (pintype "bidirectional"))
      (node (ref "U3") (pin "6") (pinfunction "SCL_6") (pintype "input"))
    )
    (net (code "43") (name "/SDA") (class "Default")
      (node (ref "I2C01") (pin "3") (pinfunction "3_3") (pintype "passive"))
      (node (ref "I2C02") (pin "3") (pinfunction "3_3") (pintype "passive"))
      (node (ref "I2C03") (pin "3") (pinfunction "3_3") (pintype "passive"))
      (node (ref "IC4") (pin "7") (pinfunction "SDA/SDI_7") (pintype "bidirectional"))
      (node (ref "R9") (pin "1") (pinfunction "1_1") (pintype "passive"))
      (node (ref "U1") (pin "19") (pinfunction "(SDA/INT1)PD1_19") (pintype "bidirectional"))
      (node (ref "U2") (pin "19") (pinfunction "(SDA/INT1)PD1_19") (pintype "bidirectional"))
      (node (ref "U3") (pin "5") (pinfunction "SDA_5") (pintype "bidirectional"))
    )
    (net (code "44") (name "/TX") (class "Default")
      (node (ref "JP3") (pin "1") (pinfunction "1_1") (pintype "passive"))
      (node (ref "U1") (pin "21") (pinfunction "(TXD1/INT3)PD3_21") (pintype "bidirectional"))
      (node (ref "U2") (pin "21") (pinfunction "(TXD1/INT3)PD3_21") (pintype "bidirectional"))
    )
    (net (code "45") (name "/TX_LED") (class "Default")
      (node (ref "TX") (pin "C") (pinfunction "C_C") (pintype "passive"))
      (node (ref "U1") (pin "22") (pinfunction "(XCK1/#CTS)PD5_22") (pintype "bidirectional"))
      (node (ref "U2") (pin "22") (pinfunction "(XCK1/#CTS)PD5_22") (pintype "bidirectional"))
    )
    (net (code "46") (name "/UCAP") (class "Default")
      (node (ref "C5") (pin "1") (pinfunction "1_1") (pintype "passive"))
      (node (ref "U1") (pin "6") (pinfunction "UCAP_6") (pintype "passive"))
      (node (ref "U2") (pin "6") (pinfunction "UCAP_6") (pintype "passive"))
    )
    (net (code "47") (name "/VP1") (class "Default")
      (node (ref "PTZ3") (pin "P$42") (pinfunction "1_P$42") (pintype "power_in"))
      (node (ref "SJ1") (pin "2") (pinfunction "2_2") (pintype "passive"))
    )
    (net (code "48") (name "/VP2") (class "Default")
      (node (ref "PTZ4") (pin "P$42") (pinfunction "1_P$42") (pintype "power_in"))
      (node (ref "SJ2") (pin "2") (pinfunction "2_2") (pintype "passive"))
    )
    (net (code "49") (name "/VP3") (class "Default")
      (node (ref "PTZ1") (pin "P$42") (pinfunction "1_P$42") (pintype "power_in"))
      (node (ref "SJ3") (pin "2") (pinfunction "2_2") (pintype "passive"))
    )
    (net (code "50") (name "/VP4") (class "Default")
      (node (ref "PTZ2") (pin "P$42") (pinfunction "1_P$42") (pintype "power_in"))
      (node (ref "SJ4") (pin "2") (pinfunction "2_2") (pintype "passive"))
    )
    (net (code "51") (name "/VUSB") (class "Default")
      (node (ref "C7") (pin "+") (pinfunction "+_+") (pintype "passive"))
      (node (ref "C8") (pin "+") (pinfunction "+_+") (pintype "passive"))
      (node (ref "C9") (pin "1") (pinfunction "1_1") (pintype "passive"))
      (node (ref "F1") (pin "2") (pinfunction "2_2") (pintype "passive"))
      (node (ref "JP3") (pin "7") (pinfunction "7_7") (pintype "passive"))
      (node (ref "JP3") (pin "8") (pinfunction "8_8") (pintype "passive"))
      (node (ref "SJ5") (pin "1") (pinfunction "1_1") (pintype "passive"))
      (node (ref "U1") (pin "7") (pinfunction "VBUS_7") (pintype "input"))
      (node (ref "U2") (pin "7") (pinfunction "VBUS_7") (pintype "input"))
    )
    (net (code "52") (name "/X0") (class "Default")
      (node (ref "IC1") (pin "9") (pinfunction "X0_9") (pintype "input"))
      (node (ref "S0") (pin "1") (pinfunction "1_1") (pintype "passive"))
      (node (ref "S0.1") (pin "1") (pinfunction "1_1") (pintype "passive"))
      (node (ref "TK0") (pin "2") (pinfunction "2_2") (pintype "passive"))
    )
    (net (code "53") (name "/X1") (class "Default")
      (node (ref "IC1") (pin "8") (pinfunction "X1_8") (pintype "input"))
      (node (ref "S1") (pin "1") (pinfunction "1_1") (pintype "passive"))
      (node (ref "S1.1") (pin "1") (pinfunction "1_1") (pintype "passive"))
      (node (ref "TK1") (pin "2") (pinfunction "2_2") (pintype "passive"))
    )
    (net (code "54") (name "/X2") (class "Default")
      (node (ref "IC1") (pin "7") (pinfunction "X2_7") (pintype "input"))
      (node (ref "S2") (pin "1") (pinfunction "1_1") (pintype "passive"))
      (node (ref "S2.1") (pin "1") (pinfunction "1_1") (pintype "passive"))
      (node (ref "TK2") (pin "2") (pinfunction "2_2") (pintype "passive"))
    )
    (net (code "55") (name "/X3") (class "Default")
      (node (ref "IC1") (pin "6") (pinfunction "X3_6") (pintype "input"))
      (node (ref "S3") (pin "1") (pinfunction "1_1") (pintype "passive"))
      (node (ref "S3.1") (pin "1") (pinfunction "1_1") (pintype "passive"))
      (node (ref "TK3") (pin "2") (pinfunction "2_2") (pintype "passive"))
    )
    (net (code "56") (name "/X4") (class "Default")
      (node (ref "IC1") (pin "5") (pinfunction "X4_5") (pintype "input"))
      (node (ref "S4") (pin "1") (pinfunction "1_1") (pintype "passive"))
      (node (ref "S4.1") (pin "1") (pinfunction "1_1") (pintype "passive"))
      (node (ref "TK4") (pin "2") (pinfunction "2_2") (pintype "passive"))
    )
    (net (code "57") (name "/X5") (class "Default")
      (node (ref "IC1") (pin "4") (pinfunction "X5_4") (pintype "input"))
      (node (ref "S5") (pin "1") (pinfunction "1_1") (pintype "passive"))
      (node (ref "S5.1") (pin "1") (pinfunction "1_1") (pintype "passive"))
      (node (ref "TK5") (pin "2") (pinfunction "2_2") (pintype "passive"))
    )
    (net (code "58") (name "/X6") (class "Default")
      (node (ref "IC1") (pin "3") (pinfunction "X6_3") (pintype "input"))
      (node (ref "S6") (pin "1") (pinfunction "1_1") (pintype "passive"))
      (node (ref "S6.1") (pin "1") (pinfunction "1_1") (pintype "passive"))
      (node (ref "TK6") (pin "2") (pinfunction "2_2") (pintype "passive"))
    )
    (net (code "59") (name "/X7") (class "Default")
      (node (ref "IC1") (pin "2") (pinfunction "X7_2") (pintype "input"))
      (node (ref "S7") (pin "1") (pinfunction "1_1") (pintype "passive"))
      (node (ref "S7.1") (pin "1") (pinfunction "1_1") (pintype "passive"))
      (node (ref "TK7") (pin "2") (pinfunction "2_2") (pintype "passive"))
    )
    (net (code "60") (name "/XUSB") (class "Default")
      (node (ref "F1") (pin "1") (pinfunction "1_1") (pintype "passive"))
      (node (ref "X2") (pin "1") (pinfunction "1_1") (pintype "bidirectional"))
    )
    (net (code "61") (name "AGND") (class "Default")
      (node (ref "C1") (pin "1") (pinfunction "1_1") (pintype "passive"))
      (node (ref "NM2") (pin "1") (pinfunction "1_1") (pintype "passive"))
      (node (ref "U1") (pin "43") (pinfunction "GND3_43") (pintype "power_in"))
      (node (ref "U2") (pin "43") (pinfunction "GND3_43") (pintype "power_in"))
    )
    (net (code "62") (name "GND") (class "Default")
      (node (ref "C10") (pin "-") (pinfunction "-_-") (pintype "passive"))
      (node (ref "C11") (pin "2") (pinfunction "2_2") (pintype "passive"))
      (node (ref "C12") (pin "2") (pinfunction "2_2") (pintype "passive"))
      (node (ref "C13") (pin "2") (pinfunction "2_2") (pintype "passive"))
      (node (ref "C16") (pin "2") (pinfunction "2_2") (pintype "passive"))
      (node (ref "C2") (pin "1") (pinfunction "1_1") (pintype "passive"))
      (node (ref "C3") (pin "1") (pinfunction "1_1") (pintype "passive"))
      (node (ref "C4") (pin "2") (pinfunction "2_2") (pintype "passive"))
      (node (ref "C6") (pin "2") (pinfunction "2_2") (pintype "passive"))
      (node (ref "C7") (pin "-") (pinfunction "-_-") (pintype "passive"))
      (node (ref "C8") (pin "-") (pinfunction "-_-") (pintype "passive"))
      (node (ref "C9") (pin "2") (pinfunction "2_2") (pintype "passive"))
      (node (ref "H1") (pin "P$1") (pinfunction "PAD_P$1") (pintype "bidirectional"))
      (node (ref "H2") (pin "P$1") (pinfunction "PAD_P$1") (pintype "bidirectional"))
      (node (ref "H3") (pin "P$1") (pinfunction "PAD_P$1") (pintype "bidirectional"))
      (node (ref "H4") (pin "P$1") (pinfunction "PAD_P$1") (pintype "bidirectional"))
      (node (ref "H5") (pin "P$1") (pinfunction "PAD_P$1") (pintype "bidirectional"))
      (node (ref "H6") (pin "P$1") (pinfunction "PAD_P$1") (pintype "bidirectional"))
      (node (ref "H7") (pin "P$1") (pinfunction "PAD_P$1") (pintype "bidirectional"))
      (node (ref "H8") (pin "P$1") (pinfunction "PAD_P$1") (pintype "bidirectional"))
      (node (ref "I2C01") (pin "1") (pinfunction "1_1") (pintype "passive"))
      (node (ref "I2C02") (pin "1") (pinfunction "1_1") (pintype "passive"))
      (node (ref "I2C03") (pin "1") (pinfunction "1_1") (pintype "passive"))
      (node (ref "IC1") (pin "12") (pinfunction "VSS_12") (pintype "power_in"))
      (node (ref "IC1") (pin "15") (pinfunction "INH_15") (pintype "input"))
      (node (ref "IC4") (pin "5") (pinfunction "GND_5") (pintype "power_in"))
      (node (ref "J1") (pin "6") (pinfunction "6_6") (pintype "passive"))
      (node (ref "JP1") (pin "10") (pinfunction "10_10") (pintype "passive"))
      (node (ref "JP2") (pin "1") (pinfunction "1_1") (pintype "passive"))
      (node (ref "JP3") (pin "5") (pinfunction "5_5") (pintype "passive"))
      (node (ref "JP3") (pin "6") (pinfunction "6_6") (pintype "passive"))
      (node (ref "NM1") (pin "1") (pinfunction "1_1") (pintype "passive"))
      (node (ref "NM2") (pin "2") (pinfunction "2_2") (pintype "passive"))
      (node (ref "P1") (pin "A") (pinfunction "A_A") (pintype "passive"))
      (node (ref "PTZ1") (pin "P$52") (pinfunction "2_P$52") (pintype "power_in"))
      (node (ref "PTZ2") (pin "P$52") (pinfunction "2_P$52") (pintype "power_in"))
      (node (ref "PTZ3") (pin "P$52") (pinfunction "2_P$52") (pintype "power_in"))
      (node (ref "PTZ4") (pin "P$52") (pinfunction "2_P$52") (pintype "power_in"))
      (node (ref "PWR") (pin "C") (pinfunction "C_C") (pintype "passive"))
      (node (ref "R6") (pin "1") (pinfunction "1_1") (pintype "passive"))
      (node (ref "RN3") (pin "5") (pinfunction "2_5") (pintype "passive"))
      (node (ref "RN3") (pin "8") (pinfunction "2_8") (pintype "passive"))
      (node (ref "S0") (pin "2") (pinfunction "2_2") (pintype "passive"))
      (node (ref "S0.1") (pin "2") (pinfunction "2_2") (pintype "passive"))
      (node (ref "S1") (pin "2") (pinfunction "2_2") (pintype "passive"))
      (node (ref "S1.1") (pin "2") (pinfunction "2_2") (pintype "passive"))
      (node (ref "S10") (pin "P$1") (pinfunction "1_P$1") (pintype "passive"))
      (node (ref "S10") (pin "P$2") (pinfunction "2_P$2") (pintype "passive"))
      (node (ref "S11") (pin "P$3") (pinfunction "3_P$3") (pintype "passive"))
      (node (ref "S11") (pin "P$4") (pinfunction "4_P$4") (pintype "passive"))
      (node (ref "S12") (pin "P$1") (pinfunction "1_P$1") (pintype "passive"))
      (node (ref "S12") (pin "P$2") (pinfunction "2_P$2") (pintype "passive"))
      (node (ref "S13") (pin "P$1") (pinfunction "1_P$1") (pintype "passive"))
      (node (ref "S13") (pin "P$2") (pinfunction "2_P$2") (pintype "passive"))
      (node (ref "S14") (pin "P$1") (pinfunction "1_P$1") (pintype "passive"))
      (node (ref "S14") (pin "P$2") (pinfunction "2_P$2") (pintype "passive"))
      (node (ref "S2") (pin "2") (pinfunction "2_2") (pintype "passive"))
      (node (ref "S2.1") (pin "2") (pinfunction "2_2") (pintype "passive"))
      (node (ref "S3") (pin "2") (pinfunction "2_2") (pintype "passive"))
      (node (ref "S3.1") (pin "2") (pinfunction "2_2") (pintype "passive"))
      (node (ref "S4") (pin "2") (pinfunction "2_2") (pintype "passive"))
      (node (ref "S4.1") (pin "2") (pinfunction "2_2") (pintype "passive"))
      (node (ref "S5") (pin "2") (pinfunction "2_2") (pintype "passive"))
      (node (ref "S5.1") (pin "2") (pinfunction "2_2") (pintype "passive"))
      (node (ref "S6") (pin "2") (pinfunction "2_2") (pintype "passive"))
      (node (ref "S6.1") (pin "2") (pinfunction "2_2") (pintype "passive"))
      (node (ref "S7") (pin "2") (pinfunction "2_2") (pintype "passive"))
      (node (ref "S7.1") (pin "2") (pinfunction "2_2") (pintype "passive"))
      (node (ref "S8") (pin "3") (pinfunction "3_3") (pintype "passive"))
      (node (ref "S8") (pin "4") (pinfunction "4_4") (pintype "passive"))
      (node (ref "T1") (pin "2") (pinfunction "E_2") (pintype "passive"))
      (node (ref "TK0") (pin "1") (pinfunction "1_1") (pintype "passive"))
      (node (ref "TK1") (pin "1") (pinfunction "1_1") (pintype "passive"))
      (node (ref "TK2") (pin "1") (pinfunction "1_1") (pintype "passive"))
      (node (ref "TK3") (pin "1") (pinfunction "1_1") (pintype "passive"))
      (node (ref "TK4") (pin "1") (pinfunction "1_1") (pintype "passive"))
      (node (ref "TK5") (pin "1") (pinfunction "1_1") (pintype "passive"))
      (node (ref "TK6") (pin "1") (pinfunction "1_1") (pintype "passive"))
      (node (ref "TK7") (pin "1") (pinfunction "1_1") (pintype "passive"))
      (node (ref "TKD0") (pin "1") (pinfunction "1_1") (pintype "passive"))
      (node (ref "TKD1") (pin "1") (pinfunction "1_1") (pintype "passive"))
      (node (ref "TKD2") (pin "1") (pinfunction "1_1") (pintype "passive"))
      (node (ref "TKD3") (pin "1") (pinfunction "1_1") (pintype "passive"))
      (node (ref "TKD4") (pin "1") (pinfunction "1_1") (pintype "passive"))
      (node (ref "TKD5") (pin "1") (pinfunction "1_1") (pintype "passive"))
      (node (ref "U1") (pin "15") (pinfunction "GND_15") (pintype "power_in"))
      (node (ref "U1") (pin "23") (pinfunction "GND1_23") (pintype "power_in"))
      (node (ref "U1") (pin "35") (pinfunction "GND2_35") (pintype "power_in"))
      (node (ref "U1") (pin "P$1") (pinfunction "PAD_P$1") (pintype "power_in"))
      (node (ref "U2") (pin "15") (pinfunction "GND_15") (pintype "power_in"))
      (node (ref "U2") (pin "23") (pinfunction "GND1_23") (pintype "power_in"))
      (node (ref "U2") (pin "35") (pinfunction "GND2_35") (pintype "power_in"))
      (node (ref "U2") (pin "EXP") (pinfunction "PAD_EXP") (pintype "power_in"))
      (node (ref "U3") (pin "1") (pinfunction "A0_1") (pintype "input"))
      (node (ref "U3") (pin "2") (pinfunction "A1_2") (pintype "input"))
      (node (ref "U3") (pin "3") (pinfunction "A2_3") (pintype "input"))
      (node (ref "U3") (pin "4") (pinfunction "GND_4") (pintype "passive"))
      (node (ref "U3") (pin "7") (pinfunction "WP_7") (pintype "input"))
      (node (ref "US0") (pin "3") (pinfunction "3_3") (pintype "passive"))
      (node (ref "US0") (pin "4") (pinfunction "4_4") (pintype "passive"))
      (node (ref "US0.1") (pin "3") (pinfunction "3_3") (pintype "passive"))
      (node (ref "US0.1") (pin "4") (pinfunction "4_4") (pintype "passive"))
      (node (ref "US1") (pin "3") (pinfunction "3_3") (pintype "passive"))
      (node (ref "US1") (pin "4") (pinfunction "4_4") (pintype "passive"))
      (node (ref "US1.1") (pin "3") (pinfunction "3_3") (pintype "passive"))
      (node (ref "US1.1") (pin "4") (pinfunction "4_4") (pintype "passive"))
      (node (ref "US2") (pin "3") (pinfunction "3_3") (pintype "passive"))
      (node (ref "US2") (pin "4") (pinfunction "4_4") (pintype "passive"))
      (node (ref "US2.1") (pin "3") (pinfunction "3_3") (pintype "passive"))
      (node (ref "US2.1") (pin "4") (pinfunction "4_4") (pintype "passive"))
      (node (ref "US3") (pin "3") (pinfunction "3_3") (pintype "passive"))
      (node (ref "US3") (pin "4") (pinfunction "4_4") (pintype "passive"))
      (node (ref "US3.1") (pin "3") (pinfunction "3_3") (pintype "passive"))
      (node (ref "US3.1") (pin "4") (pinfunction "4_4") (pintype "passive"))
      (node (ref "X1") (pin "2") (pinfunction "GND_2") (pintype "passive"))
      (node (ref "X1") (pin "4") (pinfunction "GND_4") (pintype "passive"))
    )
    (net (code "63") (name "Net-(IC4-~{MCLR})") (class "Default")
      (node (ref "IC4") (pin "4") (pinfunction "~{MCLR}_4") (pintype "input"))
      (node (ref "R11") (pin "2") (pinfunction "2_2") (pintype "passive"))
    )
    (net (code "64") (name "Net-(L2-Pad1)") (class "Default")
      (node (ref "L2") (pin "1") (pinfunction "1_1") (pintype "passive"))
      (node (ref "R7") (pin "2") (pinfunction "2_2") (pintype "passive"))
      (node (ref "R8") (pin "2") (pinfunction "2_2") (pintype "passive"))
      (node (ref "X2") (pin "P$1") (pinfunction "P$1_P$1") (pintype "bidirectional"))
      (node (ref "X2") (pin "P$2") (pinfunction "P$2_P$2") (pintype "bidirectional"))
    )
    (net (code "65") (name "Net-(PWR-PadA)") (class "Default")
      (node (ref "PWR") (pin "A") (pinfunction "A_A") (pintype "passive"))
      (node (ref "RN2") (pin "1") (pinfunction "1_1") (pintype "passive"))
    )
    (net (code "66") (name "Net-(RN1A-2)") (class "Default")
      (node (ref "R8") (pin "1") (pinfunction "1_1") (pintype "passive"))
      (node (ref "RN1") (pin "8") (pinfunction "2_8") (pintype "passive"))
      (node (ref "X2") (pin "2") (pinfunction "2_2") (pintype "bidirectional"))
    )
    (net (code "67") (name "Net-(RN1D-2)") (class "Default")
      (node (ref "R7") (pin "1") (pinfunction "1_1") (pintype "passive"))
      (node (ref "RN1") (pin "5") (pinfunction "2_5") (pintype "passive"))
      (node (ref "X2") (pin "3") (pinfunction "3_3") (pintype "bidirectional"))
    )
    (net (code "68") (name "Net-(RN2C-1)") (class "Default")
      (node (ref "LED") (pin "A") (pinfunction "A_A") (pintype "passive"))
      (node (ref "RN2") (pin "3") (pinfunction "1_3") (pintype "passive"))
    )
    (net (code "69") (name "Net-(RN2D-1)") (class "Default")
      (node (ref "RN2") (pin "4") (pinfunction "1_4") (pintype "passive"))
      (node (ref "TX") (pin "A") (pinfunction "A_A") (pintype "passive"))
    )
    (net (code "70") (name "Net-(S11-1)") (class "Default")
      (node (ref "R_S2") (pin "1") (pinfunction "1_1") (pintype "passive"))
      (node (ref "R_S3") (pin "2") (pinfunction "2_2") (pintype "passive"))
      (node (ref "S11") (pin "P$1") (pinfunction "1_P$1") (pintype "passive"))
      (node (ref "S11") (pin "P$2") (pinfunction "2_P$2") (pintype "passive"))
    )
    (net (code "71") (name "Net-(S12-3)") (class "Default")
      (node (ref "R_S3") (pin "1") (pinfunction "1_1") (pintype "passive"))
      (node (ref "R_S4") (pin "2") (pinfunction "2_2") (pintype "passive"))
      (node (ref "S12") (pin "P$3") (pinfunction "3_P$3") (pintype "passive"))
      (node (ref "S12") (pin "P$4") (pinfunction "4_P$4") (pintype "passive"))
    )
    (net (code "72") (name "Net-(S13-3)") (class "Default")
      (node (ref "R_S4") (pin "1") (pinfunction "1_1") (pintype "passive"))
      (node (ref "R_S5") (pin "2") (pinfunction "2_2") (pintype "passive"))
      (node (ref "S13") (pin "P$3") (pinfunction "3_P$3") (pintype "passive"))
      (node (ref "S13") (pin "P$4") (pinfunction "4_P$4") (pintype "passive"))
    )
    (net (code "73") (name "Net-(S14-3)") (class "Default")
      (node (ref "R_S5") (pin "1") (pinfunction "1_1") (pintype "passive"))
      (node (ref "S14") (pin "P$3") (pinfunction "3_P$3") (pintype "passive"))
      (node (ref "S14") (pin "P$4") (pinfunction "4_P$4") (pintype "passive"))
    )
    (net (code "74") (name "Net-(SG1-2)") (class "Default")
      (node (ref "SG1") (pin "-") (pinfunction "2_-") (pintype "passive"))
      (node (ref "T1") (pin "3") (pinfunction "C_3") (pintype "passive"))
    )
    (net (code "75") (name "Net-(T1-B)") (class "Default")
      (node (ref "R4") (pin "1") (pinfunction "1_1") (pintype "passive"))
      (node (ref "T1") (pin "1") (pinfunction "B_1") (pintype "passive"))
    )
    (net (code "76") (name "UGND") (class "Default")
      (node (ref "C5") (pin "2") (pinfunction "2_2") (pintype "passive"))
      (node (ref "L2") (pin "2") (pinfunction "2_2") (pintype "passive"))
      (node (ref "NM1") (pin "2") (pinfunction "2_2") (pintype "passive"))
      (node (ref "U1") (pin "5") (pinfunction "UGND_5") (pintype "power_in"))
      (node (ref "U2") (pin "5") (pinfunction "UGND_5") (pintype "power_in"))
      (node (ref "X2") (pin "4") (pinfunction "4_4") (pintype "bidirectional"))
    )
    (net (code "77") (name "unconnected-(IC4-CA1-Pad23)") (class "Default")
      (node (ref "IC4") (pin "23") (pinfunction "CA1_23") (pintype "bidirectional"))
    )
    (net (code "78") (name "unconnected-(IC4-CA2-Pad22)") (class "Default")
      (node (ref "IC4") (pin "22") (pinfunction "CA2_22") (pintype "bidirectional"))
    )
    (net (code "79") (name "unconnected-(IC4-CB1-Pad20)") (class "Default")
      (node (ref "IC4") (pin "20") (pinfunction "CB1_20") (pintype "bidirectional"))
    )
    (net (code "80") (name "unconnected-(IC4-CB2-Pad19)") (class "Default")
      (node (ref "IC4") (pin "19") (pinfunction "CB2_19") (pintype "bidirectional"))
    )
    (net (code "81") (name "unconnected-(IC4-NC-Pad3)") (class "Default")
      (node (ref "IC4") (pin "3") (pinfunction "NC_3") (pintype "no_connect"))
    )
    (net (code "82") (name "unconnected-(IC4-NC-Pad6)") (class "Default")
      (node (ref "IC4") (pin "6") (pinfunction "NC_6") (pintype "no_connect"))
    )
    (net (code "83") (name "unconnected-(IC4-NC-Pad12)") (class "Default")
      (node (ref "IC4") (pin "12") (pinfunction "NC_12") (pintype "no_connect"))
    )
    (net (code "84") (name "unconnected-(IC4-NC-Pad13)") (class "Default")
      (node (ref "IC4") (pin "13") (pinfunction "NC_13") (pintype "no_connect"))
    )
    (net (code "85") (name "unconnected-(IC4-NC-Pad15)") (class "Default")
      (node (ref "IC4") (pin "15") (pinfunction "NC_15") (pintype "no_connect"))
    )
    (net (code "86") (name "unconnected-(IC4-NC-Pad16)") (class "Default")
      (node (ref "IC4") (pin "16") (pinfunction "NC_16") (pintype "no_connect"))
    )
    (net (code "87") (name "unconnected-(IC4-NC-Pad17)") (class "Default")
      (node (ref "IC4") (pin "17") (pinfunction "NC_17") (pintype "no_connect"))
    )
    (net (code "88") (name "unconnected-(IC4-NC-Pad18)") (class "Default")
      (node (ref "IC4") (pin "18") (pinfunction "NC_18") (pintype "no_connect"))
    )
    (net (code "89") (name "unconnected-(IC4-NC-Pad21)") (class "Default")
      (node (ref "IC4") (pin "21") (pinfunction "NC_21") (pintype "no_connect"))
    )
    (net (code "90") (name "unconnected-(IC4-OF+-Pad24)") (class "Default")
      (node (ref "IC4") (pin "24") (pinfunction "OF+_24") (pintype "passive"))
    )
    (net (code "91") (name "unconnected-(IC4-OF--Pad1)") (class "Default")
      (node (ref "IC4") (pin "1") (pinfunction "OF-_1") (pintype "passive"))
    )
    (net (code "92") (name "unconnected-(IC4-PGM-Pad9)") (class "Default")
      (node (ref "IC4") (pin "9") (pinfunction "PGM_9") (pintype "passive"))
    )
    (net (code "93") (name "unconnected-(IC4-SDO-Pad8)") (class "Default")
      (node (ref "IC4") (pin "8") (pinfunction "SDO_8") (pintype "output"))
    )
    (net (code "94") (name "unconnected-(IC4-SR+-Pad2)") (class "Default")
      (node (ref "IC4") (pin "2") (pinfunction "SR+_2") (pintype "no_connect"))
    )
    (net (code "95") (name "unconnected-(IC4-SS-Pad11)") (class "Default")
      (node (ref "IC4") (pin "11") (pinfunction "SS_11") (pintype "passive"))
    )
    (net (code "96") (name "unconnected-(RN1B-1-Pad2)") (class "Default")
      (node (ref "RN1") (pin "2") (pinfunction "1_2") (pintype "passive"))
    )
    (net (code "97") (name "unconnected-(RN1B-2-Pad7)") (class "Default")
      (node (ref "RN1") (pin "7") (pinfunction "2_7") (pintype "passive"))
    )
    (net (code "98") (name "unconnected-(RN1C-1-Pad3)") (class "Default")
      (node (ref "RN1") (pin "3") (pinfunction "1_3") (pintype "passive"))
    )
    (net (code "99") (name "unconnected-(RN1C-2-Pad6)") (class "Default")
      (node (ref "RN1") (pin "6") (pinfunction "2_6") (pintype "passive"))
    )
    (net (code "100") (name "unconnected-(RN2B-1-Pad2)") (class "Default")
      (node (ref "RN2") (pin "2") (pinfunction "1_2") (pintype "passive"))
    )
    (net (code "101") (name "unconnected-(RN2B-2-Pad7)") (class "Default")
      (node (ref "RN2") (pin "7") (pinfunction "2_7") (pintype "passive"))
    )
  )
)
